# mcu.net
KiCad netlist of a schematic drawn in Altium Designer
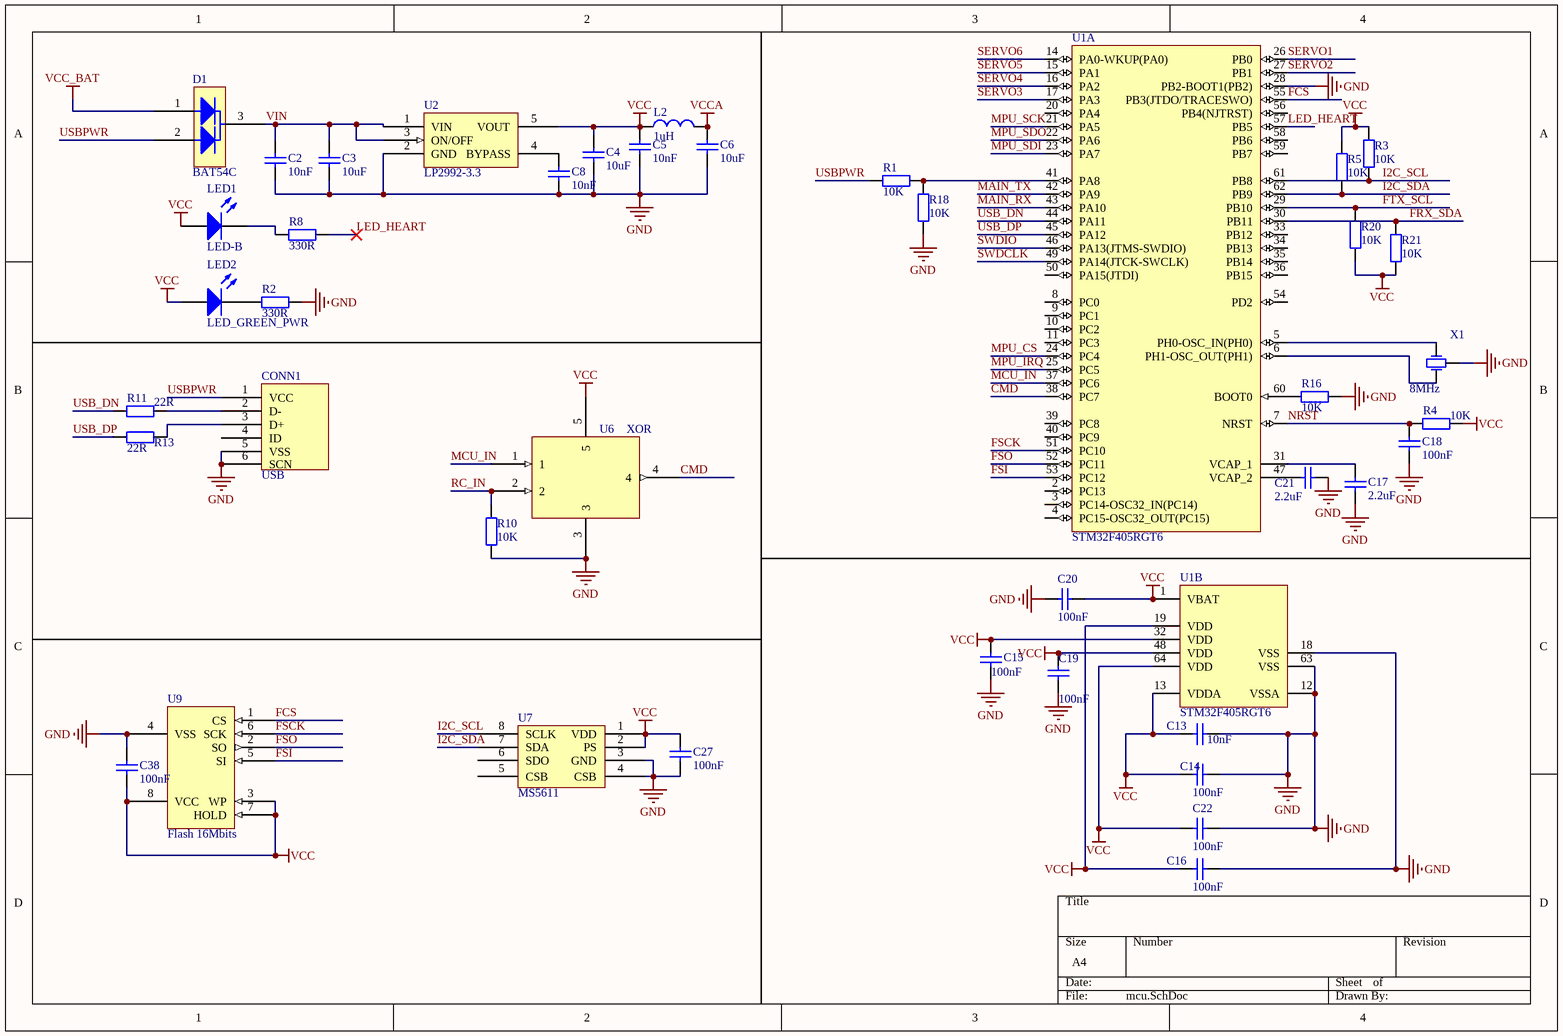
[diagram p0: mcu.SchDoc]

(export (version "E")
  (design (tool "Eeschema 10.0.6"))
  (components
    (comp (ref "C2")
      (value "10nF")
      (footprint "0402C")
      (description "贴片电阻")
      (libsource (lib "sparky") (part "cap"))
    )
    (comp (ref "C3")
      (value "10uF")
      (footprint "0805-1")
      (description "贴片电阻")
      (libsource (lib "sparky") (part "cap"))
    )
    (comp (ref "C4")
      (value "10uF")
      (footprint "0805-1")
      (description "贴片电阻")
      (libsource (lib "sparky") (part "cap"))
    )
    (comp (ref "C5")
      (value "10nF")
      (footprint "0402C")
      (description "贴片电阻")
      (libsource (lib "sparky") (part "cap"))
    )
    (comp (ref "C6")
      (value "10uF")
      (footprint "0805-1")
      (description "贴片电阻")
      (libsource (lib "sparky") (part "cap"))
    )
    (comp (ref "C8")
      (value "10nF")
      (footprint "0402C")
      (description "贴片电阻")
      (libsource (lib "sparky") (part "cap"))
    )
    (comp (ref "C13")
      (value "10nF")
      (footprint "0402C")
      (description "贴片电阻")
      (libsource (lib "sparky") (part "cap"))
    )
    (comp (ref "C14")
      (value "100nF")
      (footprint "0402C")
      (description "贴片电阻")
      (libsource (lib "sparky") (part "cap"))
    )
    (comp (ref "C15")
      (value "100nF")
      (footprint "0402C")
      (description "贴片电阻")
      (libsource (lib "sparky") (part "cap"))
    )
    (comp (ref "C16")
      (value "100nF")
      (footprint "0402C")
      (description "贴片电阻")
      (libsource (lib "sparky") (part "cap"))
    )
    (comp (ref "C17")
      (value "2.2uF")
      (footprint "0402C")
      (description "贴片电阻")
      (libsource (lib "sparky") (part "cap"))
    )
    (comp (ref "C18")
      (value "100nF")
      (footprint "0402C")
      (description "贴片电阻")
      (libsource (lib "sparky") (part "cap"))
    )
    (comp (ref "C19")
      (value "100nF")
      (footprint "0402C")
      (description "贴片电阻")
      (libsource (lib "sparky") (part "cap"))
    )
    (comp (ref "C20")
      (value "100nF")
      (footprint "0402C")
      (description "贴片电阻")
      (libsource (lib "sparky") (part "cap"))
    )
    (comp (ref "C21")
      (value "2.2uF")
      (footprint "0402C")
      (description "贴片电阻")
      (libsource (lib "sparky") (part "cap"))
    )
    (comp (ref "C22")
      (value "100nF")
      (footprint "0402C")
      (description "贴片电阻")
      (libsource (lib "sparky") (part "cap"))
    )
    (comp (ref "C27")
      (value "100nF")
      (footprint "0402C")
      (description "贴片电阻")
      (libsource (lib "sparky") (part "cap"))
    )
    (comp (ref "C38")
      (value "100nF")
      (footprint "0402C")
      (description "贴片电阻")
      (libsource (lib "sparky") (part "cap"))
    )
    (comp (ref "CONN1")
      (value "USB")
      (footprint "USB_MIC_h")
      (description "USB Micro USB R/A Type B")
      (libsource (lib "mySparky") (part "USB-MIC"))
    )
    (comp (ref "D1")
      (value "BAT54C")
      (footprint "SOT23")
      (description "Dual Diode Command Cathode BAT54C")
      (libsource (lib "sparky") (part "BAT54C"))
    )
    (comp (ref "L2")
      (value "1uH")
      (footprint "L0603")
      (description "贴片电感")
      (libsource (lib "sparky") (part "inducer"))
    )
    (comp (ref "LED1")
      (value "LED-B")
      (footprint "0402LED B")
      (description "LED-BLUE")
      (libsource (lib "sparky") (part "LED-B"))
    )
    (comp (ref "LED2")
      (value "LED_GREEN_PWR")
      (footprint "0402LED G")
      (description "绿色led")
      (libsource (lib "sparky") (part "LED_GREEN"))
    )
    (comp (ref "R1")
      (value "10K")
      (footprint "0402R")
      (description "贴片电阻")
      (libsource (lib "sparky") (part "Res-0402"))
    )
    (comp (ref "R2")
      (value "330R")
      (footprint "0402R")
      (description "贴片电阻")
      (libsource (lib "sparky") (part "Res-0402"))
    )
    (comp (ref "R3")
      (value "10K")
      (footprint "0402R")
      (description "贴片电阻")
      (libsource (lib "") (part "Res-0402_1"))
    )
    (comp (ref "R4")
      (value "10K")
      (footprint "0402R")
      (description "贴片电阻")
      (libsource (lib "sparky") (part "Res-0402"))
    )
    (comp (ref "R5")
      (value "10K")
      (footprint "0402R")
      (description "贴片电阻")
      (libsource (lib "") (part "Res-0402_1"))
    )
    (comp (ref "R8")
      (value "330R")
      (footprint "0402R")
      (description "贴片电阻")
      (libsource (lib "") (part "Res-0402_2"))
    )
    (comp (ref "R10")
      (value "10K")
      (footprint "0402R")
      (description "贴片电阻")
      (libsource (lib "") (part "Res-0402_1"))
    )
    (comp (ref "R11")
      (value "22R")
      (footprint "0402R")
      (description "贴片电阻")
      (libsource (lib "sparky") (part "Res-0402"))
    )
    (comp (ref "R13")
      (value "22R")
      (footprint "0402R")
      (description "贴片电阻")
      (libsource (lib "sparky") (part "Res-0402"))
    )
    (comp (ref "R16")
      (value "10K")
      (footprint "0402R")
      (description "贴片电阻")
      (libsource (lib "sparky") (part "Res-0402"))
    )
    (comp (ref "R18")
      (value "10K")
      (footprint "0402R")
      (description "贴片电阻")
      (libsource (lib "") (part "Res-0402_1"))
    )
    (comp (ref "R20")
      (value "10K")
      (footprint "0402R")
      (description "贴片电阻")
      (libsource (lib "") (part "Res-0402_1"))
    )
    (comp (ref "R21")
      (value "10K")
      (footprint "0402R")
      (description "贴片电阻")
      (libsource (lib "") (part "Res-0402_1"))
    )
    (comp (ref "U1")
      (value "STM32F405RGT6")
      (footprint "STM-LQFP64_N")
      (fields (field (name "MANUFACTURER") "STMicroelectronics"))
      (libsource (lib "STMicroelectronics STM32 F4") (part "STM32F405RGT6"))
    )
    (comp (ref "U2")
      (value "LP2992-3.3")
      (footprint "SOT-23-5L")
      (description "LP2992IM5-3.3/NOPBCT-ND")
      (libsource (lib "sparky") (part "LP2992-3.3"))
    )
    (comp (ref "U6")
      (value "XOR")
      (footprint "SC70-5")
      (description "XOR Gate SN74LVC1G86DCKR")
      (libsource (lib "sparky") (part "XOR"))
    )
    (comp (ref "U7")
      (value "MS5611")
      (footprint "MS5611-01BA")
      (description "MS561101BA03")
      (libsource (lib "sparky") (part "MS5611"))
    )
    (comp (ref "U9")
      (value "Flash 16Mbits")
      (footprint "SO8_N")
      (description "16Mbit SPI Flash Memory")
      (libsource (lib "Schlib1") (part "Flash"))
    )
    (comp (ref "X1") (value "8MHz") (footprint "XTAL3215") (libsource (lib "MiniFly+") (part "XTAL-3215")))
  )
  (nets
    (net (code "1") (name "/CMD") (class "Default")
      (node (ref "U1") (pin "38") (pinfunction "PC7_38") (pintype "bidirectional"))
      (node (ref "U6") (pin "4") (pinfunction "4_4") (pintype "output"))
    )
    (net (code "2") (name "/FCS") (class "Default")
      (node (ref "U1") (pin "55") (pinfunction "PB3(JTDO/TRACESWO)_55") (pintype "bidirectional"))
      (node (ref "U9") (pin "1") (pinfunction "CS_1") (pintype "input"))
    )
    (net (code "3") (name "/FRX_SDA") (class "Default")
      (node (ref "R21") (pin "2") (pinfunction "2_2") (pintype "passive"))
      (node (ref "U1") (pin "30") (pinfunction "PB11_30") (pintype "bidirectional"))
    )
    (net (code "4") (name "/FSCK") (class "Default")
      (node (ref "U1") (pin "51") (pinfunction "PC10_51") (pintype "bidirectional"))
      (node (ref "U9") (pin "6") (pinfunction "SCK_6") (pintype "input"))
    )
    (net (code "5") (name "/FSI") (class "Default")
      (node (ref "U1") (pin "53") (pinfunction "PC12_53") (pintype "bidirectional"))
      (node (ref "U9") (pin "5") (pinfunction "SI_5") (pintype "input"))
    )
    (net (code "6") (name "/FSO") (class "Default")
      (node (ref "U1") (pin "52") (pinfunction "PC11_52") (pintype "bidirectional"))
      (node (ref "U9") (pin "2") (pinfunction "SO_2") (pintype "output"))
    )
    (net (code "7") (name "/FTX_SCL") (class "Default")
      (node (ref "R20") (pin "2") (pinfunction "2_2") (pintype "passive"))
      (node (ref "U1") (pin "29") (pinfunction "PB10_29") (pintype "bidirectional"))
    )
    (net (code "8") (name "/I2C_SCL") (class "Default")
      (node (ref "R3") (pin "1") (pinfunction "1_1") (pintype "passive"))
      (node (ref "U1") (pin "61") (pinfunction "PB8_61") (pintype "bidirectional"))
      (node (ref "U7") (pin "8") (pinfunction "SCLK_8") (pintype "passive"))
    )
    (net (code "9") (name "/I2C_SDA") (class "Default")
      (node (ref "R5") (pin "1") (pinfunction "1_1") (pintype "passive"))
      (node (ref "U1") (pin "62") (pinfunction "PB9_62") (pintype "bidirectional"))
      (node (ref "U7") (pin "7") (pinfunction "SDA_7") (pintype "passive"))
    )
    (net (code "10") (name "/LED_HEART") (class "Default")
      (node (ref "R8") (pin "1") (pinfunction "1_1") (pintype "passive"))
      (node (ref "U1") (pin "57") (pinfunction "PB5_57") (pintype "bidirectional"))
    )
    (net (code "11") (name "/MAIN_RX") (class "Default")
      (node (ref "U1") (pin "43") (pinfunction "PA10_43") (pintype "bidirectional"))
    )
    (net (code "12") (name "/MAIN_TX") (class "Default")
      (node (ref "U1") (pin "42") (pinfunction "PA9_42") (pintype "bidirectional"))
    )
    (net (code "13") (name "/MCU_IN") (class "Default")
      (node (ref "U1") (pin "37") (pinfunction "PC6_37") (pintype "bidirectional"))
      (node (ref "U6") (pin "1") (pinfunction "1_1") (pintype "input"))
    )
    (net (code "14") (name "/MPU_CS") (class "Default")
      (node (ref "U1") (pin "24") (pinfunction "PC4_24") (pintype "bidirectional"))
    )
    (net (code "15") (name "/MPU_IRQ") (class "Default")
      (node (ref "U1") (pin "25") (pinfunction "PC5_25") (pintype "bidirectional"))
    )
    (net (code "16") (name "/MPU_SCK") (class "Default")
      (node (ref "U1") (pin "21") (pinfunction "PA5_21") (pintype "bidirectional"))
    )
    (net (code "17") (name "/MPU_SDI") (class "Default")
      (node (ref "U1") (pin "23") (pinfunction "PA7_23") (pintype "bidirectional"))
    )
    (net (code "18") (name "/MPU_SDO") (class "Default")
      (node (ref "U1") (pin "22") (pinfunction "PA6_22") (pintype "bidirectional"))
    )
    (net (code "19") (name "/NRST") (class "Default")
      (node (ref "C18") (pin "2") (pinfunction "2_2") (pintype "passive"))
      (node (ref "R4") (pin "1") (pinfunction "1_1") (pintype "passive"))
      (node (ref "U1") (pin "7") (pinfunction "NRST_7") (pintype "bidirectional"))
    )
    (net (code "20") (name "/RC_IN") (class "Default")
      (node (ref "R10") (pin "2") (pinfunction "2_2") (pintype "passive"))
      (node (ref "U6") (pin "2") (pinfunction "2_2") (pintype "input"))
    )
    (net (code "21") (name "/SERVO1") (class "Default")
      (node (ref "U1") (pin "26") (pinfunction "PB0_26") (pintype "bidirectional"))
    )
    (net (code "22") (name "/SERVO2") (class "Default")
      (node (ref "U1") (pin "27") (pinfunction "PB1_27") (pintype "bidirectional"))
    )
    (net (code "23") (name "/SERVO3") (class "Default")
      (node (ref "U1") (pin "17") (pinfunction "PA3_17") (pintype "bidirectional"))
    )
    (net (code "24") (name "/SERVO4") (class "Default")
      (node (ref "U1") (pin "16") (pinfunction "PA2_16") (pintype "bidirectional"))
    )
    (net (code "25") (name "/SERVO5") (class "Default")
      (node (ref "U1") (pin "15") (pinfunction "PA1_15") (pintype "bidirectional"))
    )
    (net (code "26") (name "/SERVO6") (class "Default")
      (node (ref "U1") (pin "14") (pinfunction "PA0-WKUP(PA0)_14") (pintype "bidirectional"))
    )
    (net (code "27") (name "/SWDCLK") (class "Default")
      (node (ref "U1") (pin "49") (pinfunction "PA14(JTCK-SWCLK)_49") (pintype "bidirectional"))
    )
    (net (code "28") (name "/SWDIO") (class "Default")
      (node (ref "U1") (pin "46") (pinfunction "PA13(JTMS-SWDIO)_46") (pintype "bidirectional"))
    )
    (net (code "29") (name "/USBPWR") (class "Default")
      (node (ref "CONN1") (pin "1") (pinfunction "VCC_1") (pintype "passive"))
      (node (ref "D1") (pin "2") (pinfunction "2_2") (pintype "passive"))
      (node (ref "R1") (pin "1") (pinfunction "1_1") (pintype "passive"))
    )
    (net (code "30") (name "/USB_DN") (class "Default")
      (node (ref "R11") (pin "1") (pinfunction "1_1") (pintype "passive"))
      (node (ref "U1") (pin "44") (pinfunction "PA11_44") (pintype "bidirectional"))
    )
    (net (code "31") (name "/USB_DP") (class "Default")
      (node (ref "R13") (pin "1") (pinfunction "1_1") (pintype "passive"))
      (node (ref "U1") (pin "45") (pinfunction "PA12_45") (pintype "bidirectional"))
    )
    (net (code "32") (name "/VIN") (class "Default")
      (node (ref "C2") (pin "2") (pinfunction "2_2") (pintype "passive"))
      (node (ref "C3") (pin "2") (pinfunction "2_2") (pintype "passive"))
      (node (ref "D1") (pin "3") (pinfunction "3_3") (pintype "passive"))
      (node (ref "U2") (pin "1") (pinfunction "VIN_1") (pintype "power_in"))
      (node (ref "U2") (pin "3") (pinfunction "ON/OFF_3") (pintype "input"))
    )
    (net (code "33") (name "GND") (class "Default")
      (node (ref "C13") (pin "2") (pinfunction "2_2") (pintype "passive"))
      (node (ref "C14") (pin "2") (pinfunction "2_2") (pintype "passive"))
      (node (ref "C15") (pin "1") (pinfunction "1_1") (pintype "passive"))
      (node (ref "C16") (pin "2") (pinfunction "2_2") (pintype "passive"))
      (node (ref "C17") (pin "1") (pinfunction "1_1") (pintype "passive"))
      (node (ref "C18") (pin "1") (pinfunction "1_1") (pintype "passive"))
      (node (ref "C19") (pin "1") (pinfunction "1_1") (pintype "passive"))
      (node (ref "C2") (pin "1") (pinfunction "1_1") (pintype "passive"))
      (node (ref "C20") (pin "1") (pinfunction "1_1") (pintype "passive"))
      (node (ref "C21") (pin "2") (pinfunction "2_2") (pintype "passive"))
      (node (ref "C22") (pin "2") (pinfunction "2_2") (pintype "passive"))
      (node (ref "C27") (pin "1") (pinfunction "1_1") (pintype "passive"))
      (node (ref "C3") (pin "1") (pinfunction "1_1") (pintype "passive"))
      (node (ref "C38") (pin "2") (pinfunction "2_2") (pintype "passive"))
      (node (ref "C4") (pin "1") (pinfunction "1_1") (pintype "passive"))
      (node (ref "C5") (pin "1") (pinfunction "1_1") (pintype "passive"))
      (node (ref "C6") (pin "1") (pinfunction "1_1") (pintype "passive"))
      (node (ref "C8") (pin "1") (pinfunction "1_1") (pintype "passive"))
      (node (ref "CONN1") (pin "5") (pinfunction "VSS_5") (pintype "passive"))
      (node (ref "CONN1") (pin "6") (pinfunction "SCN_6") (pintype "passive"))
      (node (ref "R10") (pin "1") (pinfunction "1_1") (pintype "passive"))
      (node (ref "R16") (pin "2") (pinfunction "2_2") (pintype "passive"))
      (node (ref "R18") (pin "1") (pinfunction "1_1") (pintype "passive"))
      (node (ref "R2") (pin "2") (pinfunction "2_2") (pintype "passive"))
      (node (ref "U1") (pin "12") (pinfunction "VSSA_12") (pintype "power_in"))
      (node (ref "U1") (pin "18") (pinfunction "VSS_18") (pintype "power_in"))
      (node (ref "U1") (pin "28") (pinfunction "PB2-BOOT1(PB2)_28") (pintype "bidirectional"))
      (node (ref "U1") (pin "63") (pinfunction "VSS_63") (pintype "power_in"))
      (node (ref "U2") (pin "2") (pinfunction "GND_2") (pintype "power_in"))
      (node (ref "U6") (pin "3") (pinfunction "3_3") (pintype "power_in"))
      (node (ref "U7") (pin "3") (pinfunction "GND_3") (pintype "passive"))
      (node (ref "U7") (pin "4") (pinfunction "CSB_4") (pintype "passive"))
      (node (ref "U9") (pin "4") (pinfunction "VSS_4") (pintype "power_in"))
      (node (ref "X1") (pin "2") (pinfunction "GND_2") (pintype "passive"))
    )
    (net (code "34") (name "Net-(CONN1-D+)") (class "Default")
      (node (ref "CONN1") (pin "3") (pinfunction "D+_3") (pintype "passive"))
      (node (ref "R13") (pin "2") (pinfunction "2_2") (pintype "passive"))
    )
    (net (code "35") (name "Net-(CONN1-D-)") (class "Default")
      (node (ref "CONN1") (pin "2") (pinfunction "D-_2") (pintype "passive"))
      (node (ref "R11") (pin "2") (pinfunction "2_2") (pintype "passive"))
    )
    (net (code "36") (name "Net-(LED1-K)") (class "Default")
      (node (ref "LED1") (pin "2") (pinfunction "K_2") (pintype "passive"))
      (node (ref "R8") (pin "2") (pinfunction "2_2") (pintype "passive"))
    )
    (net (code "37") (name "Net-(LED2-K)") (class "Default")
      (node (ref "LED2") (pin "2") (pinfunction "K_2") (pintype "passive"))
      (node (ref "R2") (pin "1") (pinfunction "1_1") (pintype "passive"))
    )
    (net (code "38") (name "Net-(U1A-BOOT0)") (class "Default")
      (node (ref "R16") (pin "1") (pinfunction "1_1") (pintype "passive"))
      (node (ref "U1") (pin "60") (pinfunction "BOOT0_60") (pintype "input"))
    )
    (net (code "39") (name "Net-(U1A-PA8)") (class "Default")
      (node (ref "R1") (pin "2") (pinfunction "2_2") (pintype "passive"))
      (node (ref "R18") (pin "2") (pinfunction "2_2") (pintype "passive"))
      (node (ref "U1") (pin "41") (pinfunction "PA8_41") (pintype "bidirectional"))
    )
    (net (code "40") (name "Net-(U1A-PH0-OSC_IN(PH0))") (class "Default")
      (node (ref "U1") (pin "5") (pinfunction "PH0-OSC_IN(PH0)_5") (pintype "bidirectional"))
      (node (ref "X1") (pin "3") (pinfunction "OSC2_3") (pintype "passive"))
    )
    (net (code "41") (name "Net-(U1A-PH1-OSC_OUT(PH1))") (class "Default")
      (node (ref "U1") (pin "6") (pinfunction "PH1-OSC_OUT(PH1)_6") (pintype "bidirectional"))
      (node (ref "X1") (pin "1") (pinfunction "OSC1_1") (pintype "passive"))
    )
    (net (code "42") (name "Net-(U1A-VCAP_1)") (class "Default")
      (node (ref "C17") (pin "2") (pinfunction "2_2") (pintype "passive"))
      (node (ref "U1") (pin "31") (pinfunction "VCAP_1_31") (pintype "power_in"))
    )
    (net (code "43") (name "Net-(U1A-VCAP_2)") (class "Default")
      (node (ref "C21") (pin "1") (pinfunction "1_1") (pintype "passive"))
      (node (ref "U1") (pin "47") (pinfunction "VCAP_2_47") (pintype "power_in"))
    )
    (net (code "44") (name "Net-(U2-BYPASS)") (class "Default")
      (node (ref "C8") (pin "2") (pinfunction "2_2") (pintype "passive"))
      (node (ref "U2") (pin "4") (pinfunction "BYPASS_4") (pintype "passive"))
    )
    (net (code "45") (name "VCC") (class "Default")
      (node (ref "C13") (pin "1") (pinfunction "1_1") (pintype "passive"))
      (node (ref "C14") (pin "1") (pinfunction "1_1") (pintype "passive"))
      (node (ref "C15") (pin "2") (pinfunction "2_2") (pintype "passive"))
      (node (ref "C16") (pin "1") (pinfunction "1_1") (pintype "passive"))
      (node (ref "C19") (pin "2") (pinfunction "2_2") (pintype "passive"))
      (node (ref "C20") (pin "2") (pinfunction "2_2") (pintype "passive"))
      (node (ref "C22") (pin "1") (pinfunction "1_1") (pintype "passive"))
      (node (ref "C27") (pin "2") (pinfunction "2_2") (pintype "passive"))
      (node (ref "C38") (pin "1") (pinfunction "1_1") (pintype "passive"))
      (node (ref "C4") (pin "2") (pinfunction "2_2") (pintype "passive"))
      (node (ref "C5") (pin "2") (pinfunction "2_2") (pintype "passive"))
      (node (ref "L2") (pin "1") (pinfunction "1_1") (pintype "passive"))
      (node (ref "LED1") (pin "1") (pinfunction "A_1") (pintype "passive"))
      (node (ref "LED2") (pin "1") (pinfunction "A_1") (pintype "passive"))
      (node (ref "R20") (pin "1") (pinfunction "1_1") (pintype "passive"))
      (node (ref "R21") (pin "1") (pinfunction "1_1") (pintype "passive"))
      (node (ref "R3") (pin "2") (pinfunction "2_2") (pintype "passive"))
      (node (ref "R4") (pin "2") (pinfunction "2_2") (pintype "passive"))
      (node (ref "R5") (pin "2") (pinfunction "2_2") (pintype "passive"))
      (node (ref "U1") (pin "1") (pinfunction "VBAT_1") (pintype "power_in"))
      (node (ref "U1") (pin "13") (pinfunction "VDDA_13") (pintype "power_in"))
      (node (ref "U1") (pin "19") (pinfunction "VDD_19") (pintype "power_in"))
      (node (ref "U1") (pin "32") (pinfunction "VDD_32") (pintype "power_in"))
      (node (ref "U1") (pin "48") (pinfunction "VDD_48") (pintype "power_in"))
      (node (ref "U1") (pin "64") (pinfunction "VDD_64") (pintype "power_in"))
      (node (ref "U2") (pin "5") (pinfunction "VOUT_5") (pintype "power_in"))
      (node (ref "U6") (pin "5") (pinfunction "5_5") (pintype "power_in"))
      (node (ref "U7") (pin "1") (pinfunction "VDD_1") (pintype "passive"))
      (node (ref "U7") (pin "2") (pinfunction "PS_2") (pintype "passive"))
      (node (ref "U9") (pin "3") (pinfunction "WP_3") (pintype "input"))
      (node (ref "U9") (pin "7") (pinfunction "HOLD_7") (pintype "input"))
      (node (ref "U9") (pin "8") (pinfunction "VCC_8") (pintype "power_in"))
    )
    (net (code "46") (name "VCCA") (class "Default")
      (node (ref "C6") (pin "2") (pinfunction "2_2") (pintype "passive"))
      (node (ref "L2") (pin "2") (pinfunction "2_2") (pintype "passive"))
    )
    (net (code "47") (name "VCC_BAT") (class "Default")
      (node (ref "D1") (pin "1") (pinfunction "1_1") (pintype "passive"))
    )
    (net (code "48") (name "unconnected-(CONN1-ID-Pad4)") (class "Default")
      (node (ref "CONN1") (pin "4") (pinfunction "ID_4") (pintype "passive"))
    )
    (net (code "49") (name "unconnected-(U1A-PA4-Pad20)") (class "Default")
      (node (ref "U1") (pin "20") (pinfunction "PA4_20") (pintype "bidirectional"))
    )
    (net (code "50") (name "unconnected-(U1A-PA15(JTDI)-Pad50)") (class "Default")
      (node (ref "U1") (pin "50") (pinfunction "PA15(JTDI)_50") (pintype "bidirectional"))
    )
    (net (code "51") (name "unconnected-(U1A-PB4(NJTRST)-Pad56)") (class "Default")
      (node (ref "U1") (pin "56") (pinfunction "PB4(NJTRST)_56") (pintype "bidirectional"))
    )
    (net (code "52") (name "unconnected-(U1A-PB6-Pad58)") (class "Default")
      (node (ref "U1") (pin "58") (pinfunction "PB6_58") (pintype "bidirectional"))
    )
    (net (code "53") (name "unconnected-(U1A-PB7-Pad59)") (class "Default")
      (node (ref "U1") (pin "59") (pinfunction "PB7_59") (pintype "bidirectional"))
    )
    (net (code "54") (name "unconnected-(U1A-PB12-Pad33)") (class "Default")
      (node (ref "U1") (pin "33") (pinfunction "PB12_33") (pintype "bidirectional"))
    )
    (net (code "55") (name "unconnected-(U1A-PB13-Pad34)") (class "Default")
      (node (ref "U1") (pin "34") (pinfunction "PB13_34") (pintype "bidirectional"))
    )
    (net (code "56") (name "unconnected-(U1A-PB14-Pad35)") (class "Default")
      (node (ref "U1") (pin "35") (pinfunction "PB14_35") (pintype "bidirectional"))
    )
    (net (code "57") (name "unconnected-(U1A-PB15-Pad36)") (class "Default")
      (node (ref "U1") (pin "36") (pinfunction "PB15_36") (pintype "bidirectional"))
    )
    (net (code "58") (name "unconnected-(U1A-PC0-Pad8)") (class "Default")
      (node (ref "U1") (pin "8") (pinfunction "PC0_8") (pintype "bidirectional"))
    )
    (net (code "59") (name "unconnected-(U1A-PC1-Pad9)") (class "Default")
      (node (ref "U1") (pin "9") (pinfunction "PC1_9") (pintype "bidirectional"))
    )
    (net (code "60") (name "unconnected-(U1A-PC2-Pad10)") (class "Default")
      (node (ref "U1") (pin "10") (pinfunction "PC2_10") (pintype "bidirectional"))
    )
    (net (code "61") (name "unconnected-(U1A-PC3-Pad11)") (class "Default")
      (node (ref "U1") (pin "11") (pinfunction "PC3_11") (pintype "bidirectional"))
    )
    (net (code "62") (name "unconnected-(U1A-PC8-Pad39)") (class "Default")
      (node (ref "U1") (pin "39") (pinfunction "PC8_39") (pintype "bidirectional"))
    )
    (net (code "63") (name "unconnected-(U1A-PC9-Pad40)") (class "Default")
      (node (ref "U1") (pin "40") (pinfunction "PC9_40") (pintype "bidirectional"))
    )
    (net (code "64") (name "unconnected-(U1A-PC13-Pad2)") (class "Default")
      (node (ref "U1") (pin "2") (pinfunction "PC13_2") (pintype "bidirectional"))
    )
    (net (code "65") (name "unconnected-(U1A-PC14-OSC32_IN(PC14)-Pad3)") (class "Default")
      (node (ref "U1") (pin "3") (pinfunction "PC14-OSC32_IN(PC14)_3") (pintype "bidirectional"))
    )
    (net (code "66") (name "unconnected-(U1A-PC15-OSC32_OUT(PC15)-Pad4)") (class "Default")
      (node (ref "U1") (pin "4") (pinfunction "PC15-OSC32_OUT(PC15)_4") (pintype "bidirectional"))
    )
    (net (code "67") (name "unconnected-(U1A-PD2-Pad54)") (class "Default")
      (node (ref "U1") (pin "54") (pinfunction "PD2_54") (pintype "bidirectional"))
    )
    (net (code "68") (name "unconnected-(U7-CSB-Pad5)") (class "Default")
      (node (ref "U7") (pin "5") (pinfunction "CSB_5") (pintype "passive"))
    )
    (net (code "69") (name "unconnected-(U7-SDO-Pad6)") (class "Default")
      (node (ref "U7") (pin "6") (pinfunction "SDO_6") (pintype "passive"))
    )
  )
)
